# MCU_nrf52840.net
KiCad netlist of a schematic drawn in Altium Designer
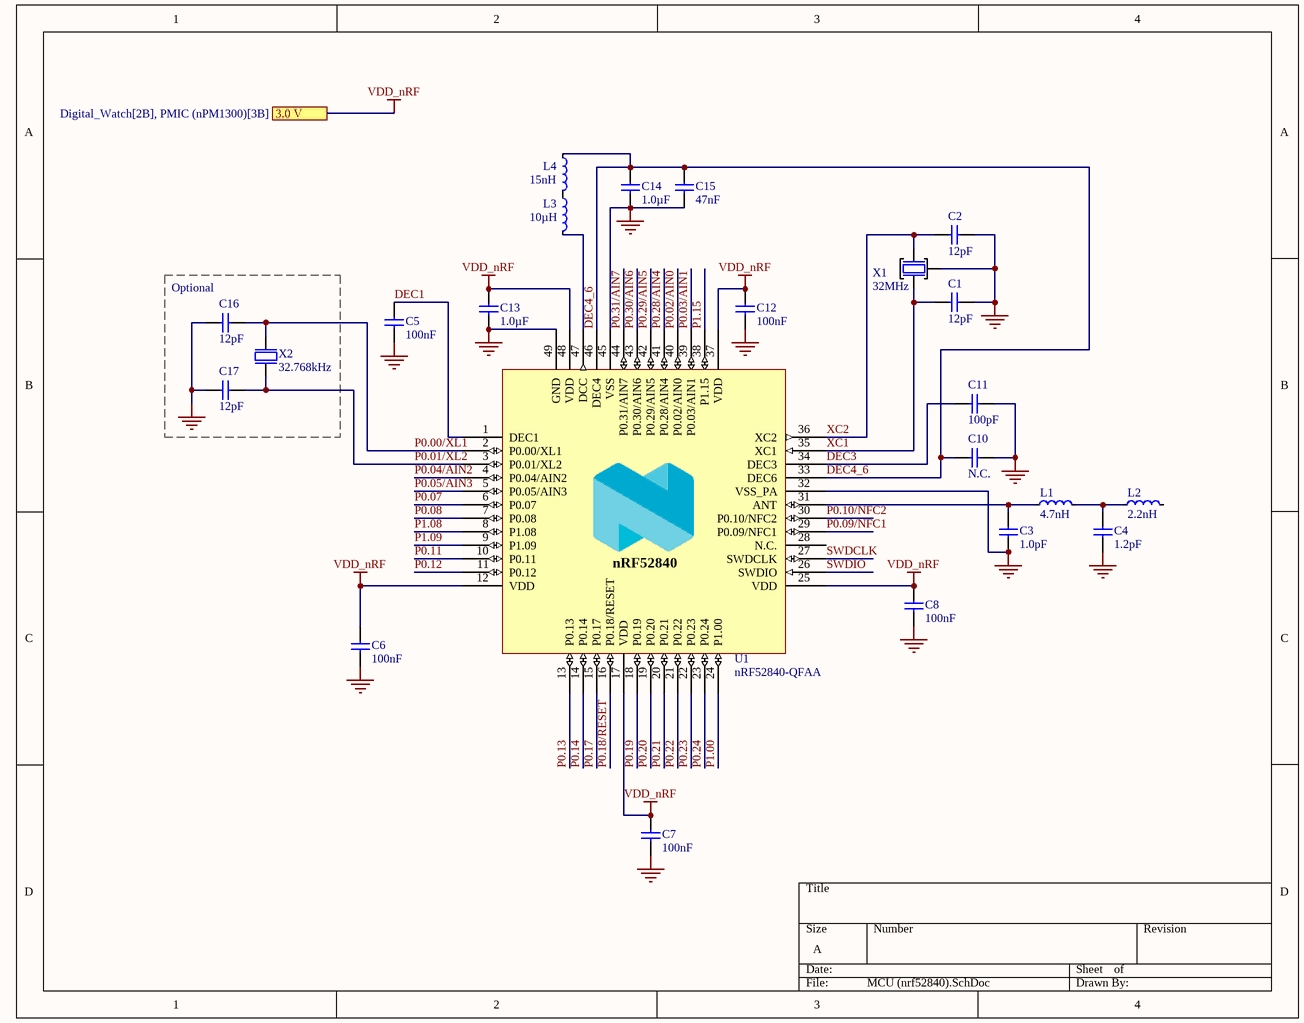
[diagram p0: MCU (nrf52840).SchDoc]

(export (version "E")
  (design (tool "Eeschema 10.0.6"))
  (components
    (comp (ref "C1")
      (value "12pF")
      (footprint "CAPC0603X03L_C")
      (description "Capacitor, NP0, ±2%")
      (fields (field (name "PART NUMBER") "C0201-12p"))
      (libsource (lib "AltiumLib") (part "CAP"))
    )
    (comp (ref "C2")
      (value "12pF")
      (footprint "CAPC0603X03L_C")
      (description "Capacitor, NP0, ±2%")
      (fields (field (name "PART NUMBER") "C0201-12p"))
      (libsource (lib "AltiumLib") (part "CAP"))
    )
    (comp (ref "C3")
      (value "1.0pF")
      (footprint "CAPC0603X03L_C")
      (description "Capacitor, NP0, ±10%")
      (fields (field (name "PART NUMBER") "C0201-1.0p"))
      (libsource (lib "AltiumLib") (part "CAP"))
    )
    (comp (ref "C4")
      (value "1.2pF")
      (footprint "CAPC0603X03L_C")
      (description "Capacitor, NP0, ±10%")
      (fields (field (name "PART NUMBER") "C0201-1.2p"))
      (libsource (lib "AltiumLib") (part "CAP"))
    )
    (comp (ref "C5")
      (value "100nF")
      (footprint "CAPC0603X03L_C")
      (description "Capacitor, X5R, ±10%")
      (fields (field (name "PART NUMBER") "C0201-100n"))
      (libsource (lib "AltiumLib") (part "CAP"))
    )
    (comp (ref "C6")
      (value "100nF")
      (footprint "CAPC0603X03L_C")
      (description "Capacitor, X5R, ±10%")
      (fields (field (name "PART NUMBER") "C0201-100n"))
      (libsource (lib "AltiumLib") (part "CAP"))
    )
    (comp (ref "C7")
      (value "100nF")
      (footprint "CAPC0603X03L_C")
      (description "Capacitor, X5R, ±10%")
      (fields (field (name "PART NUMBER") "C0201-100n"))
      (libsource (lib "AltiumLib") (part "CAP"))
    )
    (comp (ref "C8")
      (value "100nF")
      (footprint "CAPC0603X03L_C")
      (description "Capacitor, X5R, ±10%")
      (fields (field (name "PART NUMBER") "C0201-100n"))
      (libsource (lib "AltiumLib") (part "CAP"))
    )
    (comp (ref "C10")
      (value "N.C.")
      (footprint "CAPC0603X03L_C_NC")
      (description "Not mounted")
      (fields (field (name "PART NUMBER") "C0201-N.C."))
      (libsource (lib "AltiumLib") (part "CAP"))
    )
    (comp (ref "C11")
      (value "100pF")
      (footprint "CAPC0603X03L_C")
      (description "Capacitor, NP0, ±5%")
      (fields (field (name "PART NUMBER") "C0201-100p"))
      (libsource (lib "AltiumLib") (part "CAP"))
    )
    (comp (ref "C12")
      (value "100nF")
      (footprint "CAPC0603X03L_C")
      (description "Capacitor, X5R, ±10%")
      (fields (field (name "PART NUMBER") "C0201-100n"))
      (libsource (lib "AltiumLib") (part "CAP"))
    )
    (comp (ref "C13")
      (value "1.0µF")
      (footprint "CAPC1005X04L")
      (description "Capacitor, X5R, ±10%")
      (fields (field (name "PART NUMBER") "C0402-1µ0"))
      (libsource (lib "AltiumLib") (part "CAP"))
    )
    (comp (ref "C14")
      (value "1.0µF")
      (footprint "CAPC1005X04L")
      (description "Capacitor, X5R, ±10%")
      (fields (field (name "PART NUMBER") "C0402-1µ0"))
      (libsource (lib "AltiumLib") (part "CAP"))
    )
    (comp (ref "C15")
      (value "47nF")
      (footprint "CAPC0603X03L_C")
      (description "Capacitor, X5R, ±10%")
      (fields (field (name "PART NUMBER") "C0201-47n"))
      (libsource (lib "AltiumLib") (part "CAP"))
    )
    (comp (ref "C16")
      (value "12pF")
      (footprint "CAPC0603X03L_C")
      (description "Capacitor, NP0, ±2%")
      (fields (field (name "PART NUMBER") "C0201-12p"))
      (libsource (lib "AltiumLib") (part "CAP"))
    )
    (comp (ref "C17")
      (value "12pF")
      (footprint "CAPC0603X03L_C")
      (description "Capacitor, NP0, ±2%")
      (fields (field (name "PART NUMBER") "C0201-12p"))
      (libsource (lib "AltiumLib") (part "CAP"))
    )
    (comp (ref "L1")
      (value "4.7nH")
      (footprint "INDC0603X03L_C")
      (description "High frequency chip inductor ±5%")
      (fields (field (name "PART NUMBER") "L0201-4n7"))
      (libsource (lib "AltiumLib") (part "IND"))
    )
    (comp (ref "L2")
      (value "2.2nH")
      (footprint "INDC0603X03L_C")
      (description "High frequency chip inductor ±5%")
      (fields (field (name "PART NUMBER") "L0201-2n2"))
      (libsource (lib "AltiumLib") (part "IND"))
    )
    (comp (ref "L3")
      (value "10µH")
      (footprint "INDC1608X06L")
      (description "Chip inductor, IDC,min = 50 mA, ±20%")
      (fields (field (name "PART NUMBER") "L0603-10µ-TDK"))
      (libsource (lib "AltiumLib") (part "IND"))
    )
    (comp (ref "L4")
      (value "15nH")
      (footprint "INDC1005X04L")
      (description "High frequency chip inductor ±10%")
      (fields (field (name "PART NUMBER") "L0402-15n"))
      (libsource (lib "AltiumLib") (part "IND"))
    )
    (comp (ref "U1")
      (value "nRF52840-QFAA")
      (footprint "QFN40P600X600X90-48N")
      (description "Multi-protocol Bluetooth Low Energy, IEEE 802.15.4, ANT and 2.4GHz proprietary system-on-chip")
      (libsource (lib "AltiumLib") (part "nRF52840_QFAA"))
    )
    (comp (ref "X1")
      (value "32MHz")
      (footprint "XTAL_2016_NT")
      (description "XTAL SMD 2016, 32MHz, Cl=8pF, Total Tol: ±30ppm")
      (fields (field (name "PART NUMBER") "XTAL_SMD2016_32MHz_8pF_General_NT"))
      (libsource (lib "AltiumLib") (part "XTAL_4-pin_NT"))
    )
    (comp (ref "X2")
      (value "32.768kHz")
      (footprint "XTAL_2012")
      (description "XTAL SMD 2012, 32.768kHz, Cl=9pF, Total Tol: ±50ppm")
      (fields (field (name "PART NUMBER") "XTAL_SMD2012_32.768kHz_9pF_General"))
      (libsource (lib "AltiumLib") (part "XTAL_2-pin"))
    )
  )
  (nets
    (net (code "1") (name "/DEC1") (class "Default")
      (node (ref "C5") (pin "1") (pinfunction "1_1") (pintype "passive"))
      (node (ref "U1") (pin "1") (pinfunction "DEC1_1") (pintype "power_in"))
    )
    (net (code "2") (name "/DEC3") (class "Default")
      (node (ref "C11") (pin "1") (pinfunction "1_1") (pintype "passive"))
      (node (ref "U1") (pin "34") (pinfunction "DEC3_34") (pintype "power_in"))
    )
    (net (code "3") (name "/DEC4_6") (class "Default")
      (node (ref "C10") (pin "2") (pinfunction "2_2") (pintype "passive"))
      (node (ref "C14") (pin "2") (pinfunction "2_2") (pintype "passive"))
      (node (ref "C15") (pin "1") (pinfunction "1_1") (pintype "passive"))
      (node (ref "L4") (pin "1") (pinfunction "1_1") (pintype "passive"))
      (node (ref "U1") (pin "33") (pinfunction "DEC6_33") (pintype "power_in"))
      (node (ref "U1") (pin "46") (pinfunction "DEC4_46") (pintype "power_in"))
    )
    (net (code "4") (name "/P0.00{slash}XL1") (class "Default")
      (node (ref "C16") (pin "1") (pinfunction "1_1") (pintype "passive"))
      (node (ref "U1") (pin "2") (pinfunction "P0.00/XL1_2") (pintype "bidirectional"))
      (node (ref "X2") (pin "1") (pinfunction "inp_1") (pintype "passive"))
    )
    (net (code "5") (name "/P0.01{slash}XL2") (class "Default")
      (node (ref "C17") (pin "1") (pinfunction "1_1") (pintype "passive"))
      (node (ref "U1") (pin "3") (pinfunction "P0.01/XL2_3") (pintype "bidirectional"))
      (node (ref "X2") (pin "2") (pinfunction "out_2") (pintype "passive"))
    )
    (net (code "6") (name "/P0.02{slash}AIN0") (class "Default")
      (node (ref "U1") (pin "40") (pinfunction "P0.02/AIN0_40") (pintype "bidirectional"))
    )
    (net (code "7") (name "/P0.03{slash}AIN1") (class "Default")
      (node (ref "U1") (pin "39") (pinfunction "P0.03/AIN1_39") (pintype "bidirectional"))
    )
    (net (code "8") (name "/P0.04{slash}AIN2") (class "Default")
      (node (ref "U1") (pin "4") (pinfunction "P0.04/AIN2_4") (pintype "bidirectional"))
    )
    (net (code "9") (name "/P0.05{slash}AIN3") (class "Default")
      (node (ref "U1") (pin "5") (pinfunction "P0.05/AIN3_5") (pintype "bidirectional"))
    )
    (net (code "10") (name "/P0.07") (class "Default")
      (node (ref "U1") (pin "6") (pinfunction "P0.07_6") (pintype "bidirectional"))
    )
    (net (code "11") (name "/P0.08") (class "Default")
      (node (ref "U1") (pin "7") (pinfunction "P0.08_7") (pintype "bidirectional"))
    )
    (net (code "12") (name "/P0.09{slash}NFC1") (class "Default")
      (node (ref "U1") (pin "29") (pinfunction "P0.09/NFC1_29") (pintype "bidirectional"))
    )
    (net (code "13") (name "/P0.10{slash}NFC2") (class "Default")
      (node (ref "U1") (pin "30") (pinfunction "P0.10/NFC2_30") (pintype "bidirectional"))
    )
    (net (code "14") (name "/P0.11") (class "Default")
      (node (ref "U1") (pin "10") (pinfunction "P0.11_10") (pintype "bidirectional"))
    )
    (net (code "15") (name "/P0.12") (class "Default")
      (node (ref "U1") (pin "11") (pinfunction "P0.12_11") (pintype "bidirectional"))
    )
    (net (code "16") (name "/P0.13") (class "Default")
      (node (ref "U1") (pin "13") (pinfunction "P0.13_13") (pintype "bidirectional"))
    )
    (net (code "17") (name "/P0.14") (class "Default")
      (node (ref "U1") (pin "14") (pinfunction "P0.14_14") (pintype "bidirectional"))
    )
    (net (code "18") (name "/P0.17") (class "Default")
      (node (ref "U1") (pin "15") (pinfunction "P0.17_15") (pintype "bidirectional"))
    )
    (net (code "19") (name "/P0.18{slash}RESET") (class "Default")
      (node (ref "U1") (pin "16") (pinfunction "P0.18/RESET_16") (pintype "bidirectional"))
    )
    (net (code "20") (name "/P0.19") (class "Default")
      (node (ref "U1") (pin "18") (pinfunction "P0.19_18") (pintype "bidirectional"))
    )
    (net (code "21") (name "/P0.20") (class "Default")
      (node (ref "U1") (pin "19") (pinfunction "P0.20_19") (pintype "bidirectional"))
    )
    (net (code "22") (name "/P0.21") (class "Default")
      (node (ref "U1") (pin "20") (pinfunction "P0.21_20") (pintype "bidirectional"))
    )
    (net (code "23") (name "/P0.22") (class "Default")
      (node (ref "U1") (pin "21") (pinfunction "P0.22_21") (pintype "bidirectional"))
    )
    (net (code "24") (name "/P0.23") (class "Default")
      (node (ref "U1") (pin "22") (pinfunction "P0.23_22") (pintype "bidirectional"))
    )
    (net (code "25") (name "/P0.24") (class "Default")
      (node (ref "U1") (pin "23") (pinfunction "P0.24_23") (pintype "bidirectional"))
    )
    (net (code "26") (name "/P0.28{slash}AIN4") (class "Default")
      (node (ref "U1") (pin "41") (pinfunction "P0.28/AIN4_41") (pintype "bidirectional"))
    )
    (net (code "27") (name "/P0.29{slash}AIN5") (class "Default")
      (node (ref "U1") (pin "42") (pinfunction "P0.29/AIN5_42") (pintype "bidirectional"))
    )
    (net (code "28") (name "/P0.30{slash}AIN6") (class "Default")
      (node (ref "U1") (pin "43") (pinfunction "P0.30/AIN6_43") (pintype "bidirectional"))
    )
    (net (code "29") (name "/P0.31{slash}AIN7") (class "Default")
      (node (ref "U1") (pin "44") (pinfunction "P0.31/AIN7_44") (pintype "bidirectional"))
    )
    (net (code "30") (name "/P1.00") (class "Default")
      (node (ref "U1") (pin "24") (pinfunction "P1.00_24") (pintype "bidirectional"))
    )
    (net (code "31") (name "/P1.08") (class "Default")
      (node (ref "U1") (pin "8") (pinfunction "P1.08_8") (pintype "bidirectional"))
    )
    (net (code "32") (name "/P1.09") (class "Default")
      (node (ref "U1") (pin "9") (pinfunction "P1.09_9") (pintype "bidirectional"))
    )
    (net (code "33") (name "/P1.15") (class "Default")
      (node (ref "U1") (pin "38") (pinfunction "P1.15_38") (pintype "bidirectional"))
    )
    (net (code "34") (name "/SWDCLK") (class "Default")
      (node (ref "U1") (pin "27") (pinfunction "SWDCLK_27") (pintype "bidirectional"))
    )
    (net (code "35") (name "/SWDIO") (class "Default")
      (node (ref "U1") (pin "26") (pinfunction "SWDIO_26") (pintype "input"))
    )
    (net (code "36") (name "/XC1") (class "Default")
      (node (ref "C1") (pin "1") (pinfunction "1_1") (pintype "passive"))
      (node (ref "U1") (pin "35") (pinfunction "XC1_35") (pintype "input"))
      (node (ref "X1") (pin "1") (pinfunction "IN_1") (pintype "passive"))
    )
    (net (code "37") (name "/XC2") (class "Default")
      (node (ref "C2") (pin "1") (pinfunction "1_1") (pintype "passive"))
      (node (ref "U1") (pin "36") (pinfunction "XC2_36") (pintype "output"))
      (node (ref "X1") (pin "3") (pinfunction "OUT_3") (pintype "passive"))
    )
    (net (code "38") (name "GND") (class "Default")
      (node (ref "C1") (pin "2") (pinfunction "2_2") (pintype "passive"))
      (node (ref "C10") (pin "1") (pinfunction "1_1") (pintype "passive"))
      (node (ref "C11") (pin "2") (pinfunction "2_2") (pintype "passive"))
      (node (ref "C12") (pin "2") (pinfunction "2_2") (pintype "passive"))
      (node (ref "C13") (pin "2") (pinfunction "2_2") (pintype "passive"))
      (node (ref "C14") (pin "1") (pinfunction "1_1") (pintype "passive"))
      (node (ref "C15") (pin "2") (pinfunction "2_2") (pintype "passive"))
      (node (ref "C16") (pin "2") (pinfunction "2_2") (pintype "passive"))
      (node (ref "C17") (pin "2") (pinfunction "2_2") (pintype "passive"))
      (node (ref "C2") (pin "2") (pinfunction "2_2") (pintype "passive"))
      (node (ref "C3") (pin "1") (pinfunction "1_1") (pintype "passive"))
      (node (ref "C4") (pin "1") (pinfunction "1_1") (pintype "passive"))
      (node (ref "C5") (pin "2") (pinfunction "2_2") (pintype "passive"))
      (node (ref "C6") (pin "2") (pinfunction "2_2") (pintype "passive"))
      (node (ref "C7") (pin "2") (pinfunction "2_2") (pintype "passive"))
      (node (ref "C8") (pin "2") (pinfunction "2_2") (pintype "passive"))
      (node (ref "U1") (pin "32") (pinfunction "VSS_PA_32") (pintype "power_in"))
      (node (ref "U1") (pin "45") (pinfunction "VSS_45") (pintype "power_in"))
      (node (ref "U1") (pin "49") (pinfunction "GND_49") (pintype "power_in"))
      (node (ref "X1") (pin "2") (pinfunction "GND_2") (pintype "passive"))
    )
    (net (code "39") (name "Net-(C4-Pad2)") (class "Default")
      (node (ref "C4") (pin "2") (pinfunction "2_2") (pintype "passive"))
      (node (ref "L1") (pin "2") (pinfunction "2_2") (pintype "passive"))
      (node (ref "L2") (pin "1") (pinfunction "1_1") (pintype "passive"))
    )
    (net (code "40") (name "Net-(L3-Pad1)") (class "Default")
      (node (ref "L3") (pin "1") (pinfunction "1_1") (pintype "passive"))
      (node (ref "L4") (pin "2") (pinfunction "2_2") (pintype "passive"))
    )
    (net (code "41") (name "Net-(U1-ANT)") (class "Default")
      (node (ref "C3") (pin "2") (pinfunction "2_2") (pintype "passive"))
      (node (ref "L1") (pin "1") (pinfunction "1_1") (pintype "passive"))
      (node (ref "U1") (pin "31") (pinfunction "ANT_31") (pintype "bidirectional"))
    )
    (net (code "42") (name "Net-(U1-DCC)") (class "Default")
      (node (ref "L3") (pin "2") (pinfunction "2_2") (pintype "passive"))
      (node (ref "U1") (pin "47") (pinfunction "DCC_47") (pintype "output"))
    )
    (net (code "43") (name "VDD_nRF") (class "Default")
      (node (ref "C12") (pin "1") (pinfunction "1_1") (pintype "passive"))
      (node (ref "C13") (pin "1") (pinfunction "1_1") (pintype "passive"))
      (node (ref "C6") (pin "1") (pinfunction "1_1") (pintype "passive"))
      (node (ref "C7") (pin "1") (pinfunction "1_1") (pintype "passive"))
      (node (ref "C8") (pin "1") (pinfunction "1_1") (pintype "passive"))
      (node (ref "U1") (pin "12") (pinfunction "VDD_12") (pintype "power_in"))
      (node (ref "U1") (pin "17") (pinfunction "VDD_17") (pintype "power_in"))
      (node (ref "U1") (pin "25") (pinfunction "VDD_25") (pintype "power_in"))
      (node (ref "U1") (pin "37") (pinfunction "VDD_37") (pintype "power_in"))
      (node (ref "U1") (pin "48") (pinfunction "VDD_48") (pintype "power_in"))
    )
    (net (code "44") (name "unconnected-(L2-Pad2)") (class "Default")
      (node (ref "L2") (pin "2") (pinfunction "2_2") (pintype "passive"))
    )
    (net (code "45") (name "unconnected-(U1-N.C.-Pad28)") (class "Default")
      (node (ref "U1") (pin "28") (pinfunction "N.C._28") (pintype "passive"))
    )
  )
)
